# St1x.net
KiCad netlist of a schematic drawn in Altium Designer
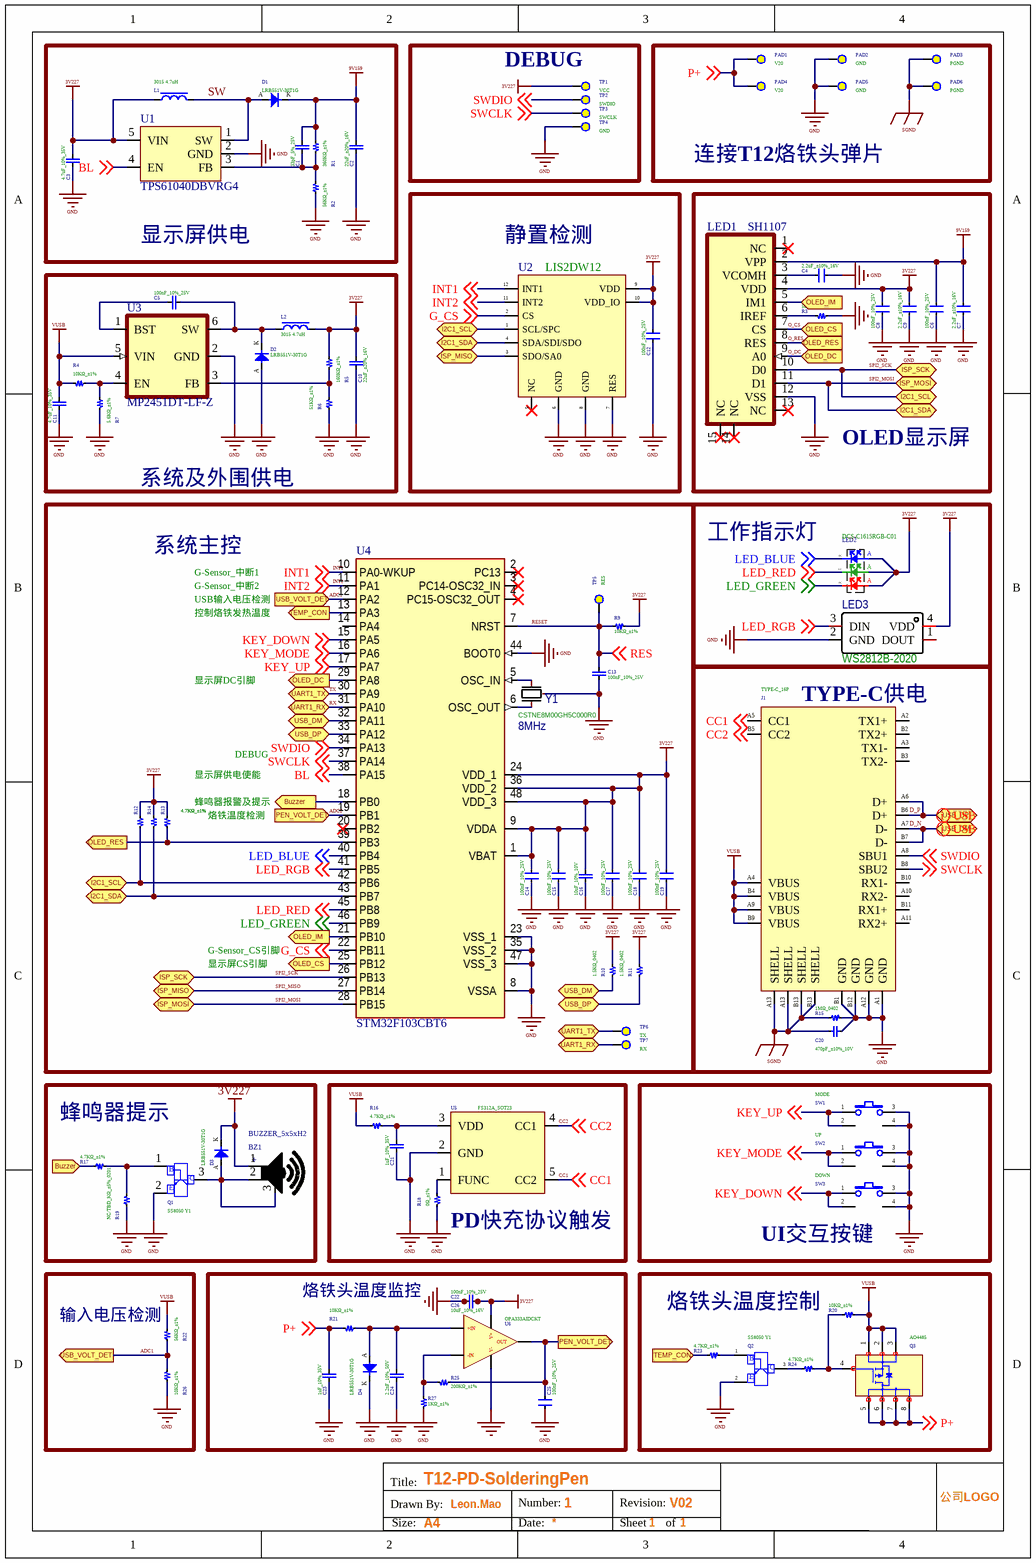
[diagram p0: St1x.SchDoc]

(export (version "E")
  (design (tool "Eeschema 10.0.6"))
  (components
    (comp (ref "BZ1")
      (value "BUZZER_5x5xH2")
      (footprint "BUZ-SMD_GSC5025YA")
      (description "电磁无源蜂鸣器(外部驱动)")
      (libsource (lib "SCHLIB_2022") (part "BZ"))
    )
    (comp (ref "C1")
      (value "33pF_5%_25V")
      (footprint "C1U0402")
      (description "贴片电容")
      (libsource (lib "SCHLIB_2022") (part "CAP_NP"))
    )
    (comp (ref "C2")
      (value "22uF_±20%_16V")
      (footprint "CL0603")
      (description "贴片电容")
      (libsource (lib "SCHLIB_2022") (part "CAP_NP"))
    )
    (comp (ref "C3")
      (value "4.7uF_10%_35V")
      (footprint "C4U0402")
      (description "贴片电容")
      (libsource (lib "SCHLIB_2022") (part "CAP_NP"))
    )
    (comp (ref "C4")
      (value "2.2uF_±10%_16V")
      (footprint "C4U0402")
      (description "贴片电容")
      (libsource (lib "") (part "CAP_NP_1"))
    )
    (comp (ref "C5")
      (value "100nF_10%_25V")
      (footprint "C1U0402")
      (description "贴片电容")
      (libsource (lib "SCHLIB_2022") (part "CAP_NP"))
    )
    (comp (ref "C6")
      (value "100nF_10%_25V")
      (footprint "C1U0402")
      (description "贴片电容")
      (libsource (lib "") (part "CAP_NP_1"))
    )
    (comp (ref "C7")
      (value "2.2uF_±10%_16V")
      (footprint "C4U0402")
      (description "贴片电容")
      (libsource (lib "") (part "CAP_NP_1"))
    )
    (comp (ref "C8")
      (value "100nF_10%_25V")
      (footprint "C1U0402")
      (description "贴片电容")
      (libsource (lib "") (part "CAP_NP_1"))
    )
    (comp (ref "C9")
      (value "2.2uF_±10%_16V")
      (footprint "C4U0402")
      (description "贴片电容")
      (libsource (lib "") (part "CAP_NP_1"))
    )
    (comp (ref "C10")
      (value "22uF_±20%_16V")
      (footprint "CL0603")
      (description "贴片电容")
      (libsource (lib "SCHLIB_2022") (part "CAP_NP"))
    )
    (comp (ref "C11")
      (value "4.7uF_10%_35V")
      (footprint "C4U0402")
      (description "贴片电容")
      (libsource (lib "SCHLIB_2022") (part "CAP_NP"))
    )
    (comp (ref "C12")
      (value "100nF_10%_25V")
      (footprint "C1U0402")
      (description "贴片电容")
      (libsource (lib "") (part "CAP_NP_1"))
    )
    (comp (ref "C13")
      (value "100nF_10%_25V")
      (footprint "C1U0402")
      (description "贴片电容")
      (libsource (lib "SCHLIB_2022") (part "CAP_NP"))
    )
    (comp (ref "C14")
      (value "100nF_10%_25V")
      (footprint "C1U0402")
      (description "贴片电容")
      (libsource (lib "") (part "CAP_NP_1"))
    )
    (comp (ref "C15")
      (value "100nF_10%_25V")
      (footprint "C1U0402")
      (description "贴片电容")
      (libsource (lib "") (part "CAP_NP_1"))
    )
    (comp (ref "C16")
      (value "10uF_10%_10V")
      (footprint "C4U0402")
      (description "贴片电容")
      (libsource (lib "SCHLIB_2022") (part "CAP_NP"))
    )
    (comp (ref "C17")
      (value "100nF_10%_25V")
      (footprint "C1U0402")
      (description "贴片电容")
      (libsource (lib "") (part "CAP_NP_1"))
    )
    (comp (ref "C18")
      (value "100nF_10%_25V")
      (footprint "C1U0402")
      (description "贴片电容")
      (libsource (lib "") (part "CAP_NP_1"))
    )
    (comp (ref "C19")
      (value "100nF_10%_25V")
      (footprint "C1U0402")
      (description "贴片电容")
      (libsource (lib "") (part "CAP_NP_1"))
    )
    (comp (ref "C20")
      (value "470pF_±10%_10V")
      (footprint "C0402")
      (description "贴片电容")
      (libsource (lib "Leon") (part "CAP NP_1"))
    )
    (comp (ref "C21")
      (value "1uF_10%_35V")
      (footprint "C1U0402")
      (description "贴片电容")
      (libsource (lib "SCHLIB_2022") (part "CAP_NP"))
    )
    (comp (ref "C22")
      (value "100nF_10%_25V")
      (footprint "C1U0402")
      (description "贴片电容")
      (libsource (lib "SCHLIB_2022") (part "CAP_NP"))
    )
    (comp (ref "C23")
      (value "1uF_10%_35V")
      (footprint "C1U0402")
      (description "贴片电容")
      (libsource (lib "SCHLIB_2022") (part "CAP_NP"))
    )
    (comp (ref "C24")
      (value "2.2nF_10%_50V")
      (footprint "C4U0402")
      (description "贴片电容")
      (libsource (lib "SCHLIB_2022") (part "CAP_NP"))
    )
    (comp (ref "C25")
      (value "100nF_10%_25V")
      (footprint "C1U0402")
      (description "贴片电容")
      (libsource (lib "") (part "CAP_NP_1"))
    )
    (comp (ref "C26")
      (value "10uF_10%_16V")
      (footprint "C4U0402")
      (description "贴片电容")
      (libsource (lib "SCHLIB_2022") (part "CAP_NP"))
    )
    (comp (ref "D1")
      (value "LRB551V-30T1G")
      (footprint "SOD-323_AK")
      (description "肖特基二极管")
      (libsource (lib "Leon") (part "DIODE"))
    )
    (comp (ref "D2")
      (value "LRB551V-30T1G")
      (footprint "SOD-323_AK")
      (description "肖特基二极管")
      (libsource (lib "Leon") (part "DIODE"))
    )
    (comp (ref "D3")
      (value "LRB551V-30T1G")
      (footprint "SOD-323_AK")
      (description "肖特基二极管")
      (libsource (lib "Leon") (part "DIODE"))
    )
    (comp (ref "D4")
      (value "LRB551V-30T1G")
      (footprint "SOD-323_AK")
      (description "肖特基二极管")
      (libsource (lib "Leon") (part "DIODE"))
    )
    (comp (ref "J1")
      (value "TYPE-C_16P")
      (footprint "TYPE-C_16P")
      (description "TYPE-C母座")
      (libsource (lib "Leon") (part "TYPE-C_RI"))
    )
    (comp (ref "L1")
      (value "3015 4.7uH")
      (footprint "INDC3015")
      (description "功率电感")
      (libsource (lib "SCHLIB_2022") (part "INDUCTOR_2"))
    )
    (comp (ref "L2")
      (value "3015 4.7uH")
      (footprint "INDC3015")
      (description "功率电感")
      (libsource (lib "") (part "INDUCTOR_2_1"))
    )
    (comp (ref "LED1")
      (value "SH1107")
      (footprint "CON_13P_0.7mm-FPC")
      (description "QG-2880TSWKG01")
      (fields
        (field (name "MF") "{'manufacturer': u'Texas Instruments'}")
        (field (name "MP") "LP2985AIM5-5.0")
      )
      (libsource (lib "SCHLIB_2022") (part "SH1107"))
    )
    (comp (ref "LED2")
      (value "DCS-C1615RGB-C01")
      (footprint "RGB_DCS-C1615RGB-C01")
      (description "红绿蓝三色发光二极管")
      (libsource (lib "Leon") (part "LED_RGBS"))
    )
    (comp (ref "LED3")
      (value "WS2812B-2020")
      (footprint "LED_2020")
      (fields (field (name "MANUFACTURER PART") "Yo-WS2812B-3528反贴雾状"))
      (libsource (lib "altium-import") (part "root_0_mirrored_YO-WS2812B-3528反贴_"))
    )
    (comp (ref "PAD1") (value "V20") (footprint "TP_A") (libsource (lib "SCHLIB_2022") (part "TEST")))
    (comp (ref "PAD2") (value "GND") (footprint "TP_A") (libsource (lib "SCHLIB_2022") (part "TEST")))
    (comp (ref "PAD3") (value "PGND") (footprint "TP_A") (libsource (lib "SCHLIB_2022") (part "TEST")))
    (comp (ref "PAD4") (value "V20") (footprint "TP_A") (libsource (lib "SCHLIB_2022") (part "TEST")))
    (comp (ref "PAD5") (value "GND") (footprint "TP_A") (libsource (lib "SCHLIB_2022") (part "TEST")))
    (comp (ref "PAD6") (value "PGND") (footprint "TP_A") (libsource (lib "SCHLIB_2022") (part "TEST")))
    (comp (ref "Q1")
      (value "SS8050 Y1")
      (footprint "SOT-23_123")
      (description "NPN三极管")
      (libsource (lib "PCBDEV_Library") (part "NPN"))
    )
    (comp (ref "Q2")
      (value "SS8050 Y1")
      (footprint "SOT-23_123")
      (description "NPN三极管")
      (libsource (lib "SCHLIB_2022") (part "NPN"))
    )
    (comp (ref "Q3")
      (value "AO4485")
      (footprint "SO-8M")
      (description "P沟道 40V 10A")
      (libsource (lib "SCHLIB_2022") (part "AO4485"))
    )
    (comp (ref "R1")
      (value "360KΩ_±1%")
      (footprint "RN0402")
      (description "贴片电阻")
      (libsource (lib "Leon") (part "ResSemi_3"))
    )
    (comp (ref "R2")
      (value "56KΩ_±1%")
      (footprint "RN0402")
      (description "贴片电阻")
      (libsource (lib "Leon") (part "ResSemi_3"))
    )
    (comp (ref "R3")
      (value "560kΩ_±1%")
      (footprint "RN0402")
      (description "贴片电阻")
      (libsource (lib "Leon") (part "ResSemi_3"))
    )
    (comp (ref "R4")
      (value "10KΩ_±1%")
      (footprint "RN0402")
      (description "贴片电阻")
      (libsource (lib "Leon") (part "ResSemi_3"))
    )
    (comp (ref "R5")
      (value "160KΩ_±1%")
      (footprint "RN0402")
      (description "贴片电阻")
      (libsource (lib "Leon") (part "ResSemi_3"))
    )
    (comp (ref "R6")
      (value "51KΩ_±1%")
      (footprint "RN0402")
      (description "贴片电阻")
      (libsource (lib "Leon") (part "ResSemi_3"))
    )
    (comp (ref "R7")
      (value "5.6KΩ_±1%")
      (footprint "RN0402")
      (description "贴片电阻")
      (libsource (lib "Leon") (part "ResSemi_3"))
    )
    (comp (ref "R9")
      (value "10KΩ_±1%")
      (footprint "RN0402")
      (description "贴片电阻")
      (libsource (lib "Leon") (part "ResSemi_3"))
    )
    (comp (ref "R10")
      (value "1.5KΩ_0402")
      (footprint "RN0402")
      (description "贴片电阻")
      (libsource (lib "Leon") (part "ResSemi_3"))
    )
    (comp (ref "R11")
      (value "1.5KΩ_0402")
      (footprint "RN0402")
      (description "贴片电阻")
      (libsource (lib "Leon") (part "ResSemi_3"))
    )
    (comp (ref "R12")
      (value "4.7KΩ_±1%")
      (footprint "RN0402")
      (description "贴片电阻")
      (libsource (lib "Leon") (part "ResSemi_3"))
    )
    (comp (ref "R13")
      (value "4.7KΩ_±1%")
      (footprint "RN0402")
      (description "贴片电阻")
      (libsource (lib "Leon") (part "ResSemi_3"))
    )
    (comp (ref "R14")
      (value "4.7KΩ_±1%")
      (footprint "RN0402")
      (description "贴片电阻")
      (libsource (lib "Leon") (part "ResSemi_3"))
    )
    (comp (ref "R15")
      (value "1MΩ_0402")
      (footprint "RN0402")
      (description "贴片电阻")
      (libsource (lib "Leon") (part "ResSemi_3"))
    )
    (comp (ref "R16")
      (value "4.7KΩ_±1%")
      (footprint "RN0402")
      (description "贴片电阻")
      (libsource (lib "Leon") (part "ResSemi_3"))
    )
    (comp (ref "R17")
      (value "4.7KΩ_±1%")
      (footprint "RN0402")
      (description "贴片电阻")
      (libsource (lib "Leon") (part "ResSemi_3"))
    )
    (comp (ref "R18")
      (value "0Ω_±1%")
      (footprint "RN0402")
      (description "贴片电阻")
      (libsource (lib "Leon") (part "ResSemi_3"))
    )
    (comp (ref "R19")
      (value "NC/TBD_KΩ_±5%_0201")
      (footprint "RN0402")
      (description "贴片电阻")
      (libsource (lib "Leon") (part "ResSemi_3"))
    )
    (comp (ref "R20")
      (value "10KΩ_±1%")
      (footprint "RN0402")
      (description "贴片电阻")
      (libsource (lib "Leon") (part "ResSemi_3"))
    )
    (comp (ref "R21")
      (value "10KΩ_±1%")
      (footprint "RN0603")
      (description "贴片电阻")
      (libsource (lib "Leon") (part "ResSemi_3"))
    )
    (comp (ref "R22")
      (value "56KΩ_±1%")
      (footprint "RN0402")
      (description "贴片电阻")
      (libsource (lib "Leon") (part "ResSemi_3"))
    )
    (comp (ref "R23")
      (value "4.7KΩ_±1%")
      (footprint "RN0402")
      (description "贴片电阻")
      (libsource (lib "Leon") (part "ResSemi_3"))
    )
    (comp (ref "R24")
      (value "4.7KΩ_±1%")
      (footprint "RN0402")
      (description "贴片电阻")
      (libsource (lib "Leon") (part "ResSemi_3"))
    )
    (comp (ref "R25")
      (value "200KΩ_±1%")
      (footprint "RN0402")
      (description "贴片电阻")
      (libsource (lib "Leon") (part "ResSemi_3"))
    )
    (comp (ref "R26")
      (value "10KΩ_±1%")
      (footprint "RN0402")
      (description "贴片电阻")
      (libsource (lib "Leon") (part "ResSemi_3"))
    )
    (comp (ref "R27")
      (value "1KΩ_±1%")
      (footprint "RN0402")
      (description "贴片电阻")
      (libsource (lib "Leon") (part "ResSemi_3"))
    )
    (comp (ref "SW1")
      (value "MODE")
      (footprint "KEY-SMD_4P-L4.2-W3.2-P2.20-LS5.1-TL")
      (description "轻触开关")
      (libsource (lib "SCHLIB_2022") (part "SW PUSHBUTTON"))
    )
    (comp (ref "SW2")
      (value "UP")
      (footprint "KEY-SMD_4P-L4.2-W3.2-P2.20-LS5.1-TL")
      (description "轻触开关")
      (libsource (lib "SCHLIB_2022") (part "SW PUSHBUTTON"))
    )
    (comp (ref "SW3")
      (value "DOWN")
      (footprint "KEY-SMD_4P-L4.2-W3.2-P2.20-LS5.1-TL")
      (description "轻触开关")
      (libsource (lib "SCHLIB_2022") (part "SW PUSHBUTTON"))
    )
    (comp (ref "TP1") (value "VCC") (footprint "SMD0808") (libsource (lib "SCHLIB_2022") (part "TEST")))
    (comp (ref "TP2") (value "SWDIO") (footprint "SMD0808") (libsource (lib "SCHLIB_2022") (part "TEST")))
    (comp (ref "TP3") (value "SWCLK") (footprint "SMD0808") (libsource (lib "SCHLIB_2022") (part "TEST")))
    (comp (ref "TP4") (value "GND") (footprint "SMD0808") (libsource (lib "SCHLIB_2022") (part "TEST")))
    (comp (ref "TP5") (value "RES") (footprint "SMD0808") (libsource (lib "SCHLIB_2022") (part "TEST")))
    (comp (ref "TP6") (value "TX") (footprint "SMD0808") (libsource (lib "SCHLIB_2022") (part "TEST")))
    (comp (ref "TP7") (value "RX") (footprint "SMD0808") (libsource (lib "SCHLIB_2022") (part "TEST")))
    (comp (ref "U1")
      (value "TPS61040DBVRG4")
      (footprint "SOT23-5")
      (description "DC-DC芯片")
      (libsource (lib "SCHLIB_2022") (part "TPS61040DBVRG4_[C7722]"))
    )
    (comp (ref "U2")
      (value "LIS2DW12")
      (footprint "LGA12_20x20x07")
      (libsource (lib "SCHLIB_2022") (part "LIS2DW12"))
    )
    (comp (ref "U3")
      (value "MP2451DT-LF-Z")
      (footprint "SOT23-6")
      (fields
        (field (name "MF") "{'manufacturer': u'Texas Instruments'}")
        (field (name "MP") "LP2985AIM5-5.0")
      )
      (libsource (lib "SCHLIB_2022") (part "MP2451DT-LF-Z"))
    )
    (comp (ref "U4")
      (value "STM32F103CBT6")
      (footprint "LQFP48-7x7mm")
      (description "No Description Available")
      (fields (field (name "COPYRIGHT") "Copyright (C) 2023 Ultra Librarian. All rights reserved."))
      (libsource (lib "SCHLIB_2022") (part "STM32F103CBT6"))
    )
    (comp (ref "U5")
      (value "FS312A_SOT23")
      (footprint "SOT23-5")
      (description "USB Type-C PD快充协议智能触发芯片")
      (libsource (lib "SCHLIB_2022") (part "FS312A"))
    )
    (comp (ref "U6")
      (value "OPA333AIDCKT")
      (footprint "SOT23-5")
      (libsource (lib "SCHLIB_2022") (part "OPA333_SOT23"))
    )
    (comp (ref "Y1")
      (value "CSTNE8M00GH5C000R0")
      (footprint "OSC-SMD_3P-L3.2-W1.3-P1.20-L")
      (description "频率:8MHz;频率容差:±0.07%;内藏负载电容:33pF;谐振阻抗:40Ω;")
      (fields (field (name "MANUFACTURER") "muRata(村田)") (field (name "ALTIUM_VALUE") "8MHz"))
      (libsource (lib "SCHLIB_2022") (part "CSTNE8M00GH5C000R0"))
    )
  )
  (nets
    (net (code "1") (name "/ADC1") (class "Default")
      (node (ref "R22") (pin "1") (pinfunction "1_1") (pintype "passive"))
      (node (ref "R26") (pin "2") (pinfunction "2_2") (pintype "passive"))
      (node (ref "U4") (pin "12") (pinfunction "PA2_12") (pintype "bidirectional"))
    )
    (net (code "2") (name "/ADC2") (class "Default")
      (node (ref "C25") (pin "1") (pinfunction "1_1") (pintype "passive"))
      (node (ref "R25") (pin "1") (pinfunction "1_1") (pintype "passive"))
      (node (ref "U4") (pin "19") (pinfunction "PB1_19") (pintype "bidirectional"))
      (node (ref "U6") (pin "1") (pinfunction "OUT_1") (pintype "passive"))
    )
    (net (code "3") (name "/Buzzer") (class "Default")
      (node (ref "R17") (pin "1") (pinfunction "1_1") (pintype "passive"))
      (node (ref "U4") (pin "18") (pinfunction "PB0_18") (pintype "bidirectional"))
    )
    (net (code "4") (name "/D_N") (class "Default")
      (node (ref "J1") (pin "A7") (pinfunction "D-_A7") (pintype "passive"))
      (node (ref "J1") (pin "B7") (pinfunction "D-_B7") (pintype "passive"))
      (node (ref "R10") (pin "2") (pinfunction "2_2") (pintype "passive"))
      (node (ref "U4") (pin "32") (pinfunction "PA11_32") (pintype "bidirectional"))
    )
    (net (code "5") (name "/D_P") (class "Default")
      (node (ref "J1") (pin "A6") (pinfunction "D+_A6") (pintype "passive"))
      (node (ref "J1") (pin "B6") (pinfunction "D+_B6") (pintype "passive"))
      (node (ref "R11") (pin "2") (pinfunction "2_2") (pintype "passive"))
      (node (ref "U4") (pin "33") (pinfunction "PA12_33") (pintype "bidirectional"))
    )
    (net (code "6") (name "/OLED_IM") (class "Default")
      (node (ref "LED1") (pin "5") (pinfunction "IM1_5") (pintype "passive"))
      (node (ref "U4") (pin "21") (pinfunction "PB10_21") (pintype "bidirectional"))
    )
    (net (code "7") (name "/O_CS") (class "Default")
      (node (ref "LED1") (pin "7") (pinfunction "CS_7") (pintype "passive"))
      (node (ref "U4") (pin "25") (pinfunction "PB12_25") (pintype "bidirectional"))
    )
    (net (code "8") (name "/O_DC") (class "Default")
      (node (ref "LED1") (pin "9") (pinfunction "A0_9") (pintype "input"))
      (node (ref "U4") (pin "29") (pinfunction "PA8_29") (pintype "bidirectional"))
    )
    (net (code "9") (name "/O_RES") (class "Default")
      (node (ref "LED1") (pin "8") (pinfunction "RES_8") (pintype "passive"))
      (node (ref "R13") (pin "2") (pinfunction "2_2") (pintype "passive"))
      (node (ref "U4") (pin "39") (pinfunction "PB3_39") (pintype "bidirectional"))
    )
    (net (code "10") (name "/RX") (class "Default")
      (node (ref "TP7") (pin "1") (pinfunction "1_1") (pintype "passive"))
      (node (ref "U4") (pin "31") (pinfunction "PA10_31") (pintype "bidirectional"))
    )
    (net (code "11") (name "/SPI2_MISO") (class "Default")
      (node (ref "U2") (pin "3") (pinfunction "SDO/SA0_3") (pintype "passive"))
      (node (ref "U4") (pin "27") (pinfunction "PB14_27") (pintype "bidirectional"))
    )
    (net (code "12") (name "/SPI2_MOSI") (class "Default")
      (node (ref "LED1") (pin "11") (pinfunction "D1_11") (pintype "passive"))
      (node (ref "R14") (pin "1") (pinfunction "1_1") (pintype "passive"))
      (node (ref "U2") (pin "4") (pinfunction "SDA/SDI/SDO_4") (pintype "passive"))
      (node (ref "U4") (pin "28") (pinfunction "PB15_28") (pintype "bidirectional"))
      (node (ref "U4") (pin "43") (pinfunction "PB7_43") (pintype "bidirectional"))
    )
    (net (code "13") (name "/SPI2_SCK") (class "Default")
      (node (ref "LED1") (pin "10") (pinfunction "D0_10") (pintype "passive"))
      (node (ref "R12") (pin "1") (pinfunction "1_1") (pintype "passive"))
      (node (ref "U2") (pin "1") (pinfunction "SCL/SPC_1") (pintype "passive"))
      (node (ref "U4") (pin "26") (pinfunction "PB13_26") (pintype "bidirectional"))
      (node (ref "U4") (pin "42") (pinfunction "PB6_42") (pintype "bidirectional"))
    )
    (net (code "14") (name "/SW") (class "Default")
      (node (ref "D1") (pin "A") (pinfunction "ANODE_A") (pintype "passive"))
      (node (ref "L1") (pin "2") (pinfunction "2_2") (pintype "passive"))
      (node (ref "U1") (pin "1") (pinfunction "SW_1") (pintype "passive"))
    )
    (net (code "15") (name "/TEMP_CON") (class "Default")
      (node (ref "R23") (pin "1") (pinfunction "1_1") (pintype "passive"))
      (node (ref "U4") (pin "13") (pinfunction "PA3_13") (pintype "bidirectional"))
    )
    (net (code "16") (name "/TX") (class "Default")
      (node (ref "TP6") (pin "1") (pinfunction "1_1") (pintype "passive"))
      (node (ref "U4") (pin "30") (pinfunction "PA9_30") (pintype "bidirectional"))
    )
    (net (code "17") (name "3V227") (class "Default")
      (node (ref "BZ1") (pin "1") (pinfunction "+_1") (pintype "passive"))
      (node (ref "C10") (pin "2") (pinfunction "2_2") (pintype "passive"))
      (node (ref "C12") (pin "1") (pinfunction "1_1") (pintype "passive"))
      (node (ref "C14") (pin "1") (pinfunction "1_1") (pintype "passive"))
      (node (ref "C15") (pin "1") (pinfunction "1_1") (pintype "passive"))
      (node (ref "C16") (pin "2") (pinfunction "2_2") (pintype "passive"))
      (node (ref "C17") (pin "1") (pinfunction "1_1") (pintype "passive"))
      (node (ref "C18") (pin "1") (pinfunction "1_1") (pintype "passive"))
      (node (ref "C19") (pin "1") (pinfunction "1_1") (pintype "passive"))
      (node (ref "C22") (pin "2") (pinfunction "2_2") (pintype "passive"))
      (node (ref "C26") (pin "1") (pinfunction "1_1") (pintype "passive"))
      (node (ref "C3") (pin "2") (pinfunction "2_2") (pintype "passive"))
      (node (ref "C8") (pin "1") (pinfunction "1_1") (pintype "passive"))
      (node (ref "C9") (pin "1") (pinfunction "1_1") (pintype "passive"))
      (node (ref "D3") (pin "K") (pinfunction "CATHODE_K") (pintype "passive"))
      (node (ref "L1") (pin "1") (pinfunction "1_1") (pintype "passive"))
      (node (ref "L2") (pin "1") (pinfunction "1_1") (pintype "passive"))
      (node (ref "LED1") (pin "4") (pinfunction "VDD_4") (pintype "power_in"))
      (node (ref "LED2") (pin "A") (pinfunction "A_A") (pintype "passive"))
      (node (ref "LED3") (pin "4") (pinfunction "VDD_4") (pintype "passive"))
      (node (ref "R10") (pin "1") (pinfunction "1_1") (pintype "passive"))
      (node (ref "R11") (pin "1") (pinfunction "1_1") (pintype "passive"))
      (node (ref "R12") (pin "2") (pinfunction "2_2") (pintype "passive"))
      (node (ref "R13") (pin "1") (pinfunction "1_1") (pintype "passive"))
      (node (ref "R14") (pin "2") (pinfunction "2_2") (pintype "passive"))
      (node (ref "R5") (pin "1") (pinfunction "1_1") (pintype "passive"))
      (node (ref "R9") (pin "1") (pinfunction "1_1") (pintype "passive"))
      (node (ref "TP1") (pin "1") (pinfunction "1_1") (pintype "passive"))
      (node (ref "U1") (pin "5") (pinfunction "VIN_5") (pintype "passive"))
      (node (ref "U2") (pin "10") (pinfunction "VDD_IO_10") (pintype "passive"))
      (node (ref "U2") (pin "9") (pinfunction "VDD_9") (pintype "passive"))
      (node (ref "U4") (pin "1") (pinfunction "VBAT_1") (pintype "power_in"))
      (node (ref "U4") (pin "24") (pinfunction "VDD_1_24") (pintype "power_in"))
      (node (ref "U4") (pin "36") (pinfunction "VDD_2_36") (pintype "power_in"))
      (node (ref "U4") (pin "48") (pinfunction "VDD_3_48") (pintype "power_in"))
      (node (ref "U4") (pin "9") (pinfunction "VDDA_9") (pintype "power_in"))
      (node (ref "U6") (pin "5") (pinfunction "V+_5") (pintype "passive"))
    )
    (net (code "18") (name "9V159") (class "Default")
      (node (ref "C1") (pin "2") (pinfunction "2_2") (pintype "passive"))
      (node (ref "C2") (pin "2") (pinfunction "2_2") (pintype "passive"))
      (node (ref "C6") (pin "1") (pinfunction "1_1") (pintype "passive"))
      (node (ref "C7") (pin "1") (pinfunction "1_1") (pintype "passive"))
      (node (ref "D1") (pin "K") (pinfunction "CATHODE_K") (pintype "passive"))
      (node (ref "LED1") (pin "2") (pinfunction "VPP_2") (pintype "power_in"))
      (node (ref "R1") (pin "1") (pinfunction "1_1") (pintype "passive"))
    )
    (net (code "19") (name "BL") (class "Default")
      (node (ref "U1") (pin "4") (pinfunction "EN_4") (pintype "passive"))
      (node (ref "U4") (pin "38") (pinfunction "PA15_38") (pintype "bidirectional"))
    )
    (net (code "20") (name "CC1") (class "Default")
      (node (ref "J1") (pin "A5") (pinfunction "CC1_A5") (pintype "passive"))
      (node (ref "U5") (pin "5") (pinfunction "CC2_5") (pintype "passive"))
    )
    (net (code "21") (name "CC2") (class "Default")
      (node (ref "J1") (pin "B5") (pinfunction "CC2_B5") (pintype "passive"))
      (node (ref "U5") (pin "4") (pinfunction "CC1_4") (pintype "passive"))
    )
    (net (code "22") (name "GND") (class "Default")
      (node (ref "C10") (pin "1") (pinfunction "1_1") (pintype "passive"))
      (node (ref "C11") (pin "1") (pinfunction "1_1") (pintype "passive"))
      (node (ref "C12") (pin "2") (pinfunction "2_2") (pintype "passive"))
      (node (ref "C13") (pin "2") (pinfunction "2_2") (pintype "passive"))
      (node (ref "C14") (pin "2") (pinfunction "2_2") (pintype "passive"))
      (node (ref "C15") (pin "2") (pinfunction "2_2") (pintype "passive"))
      (node (ref "C16") (pin "1") (pinfunction "1_1") (pintype "passive"))
      (node (ref "C17") (pin "2") (pinfunction "2_2") (pintype "passive"))
      (node (ref "C18") (pin "2") (pinfunction "2_2") (pintype "passive"))
      (node (ref "C19") (pin "2") (pinfunction "2_2") (pintype "passive"))
      (node (ref "C2") (pin "1") (pinfunction "1_1") (pintype "passive"))
      (node (ref "C20") (pin "1") (pinfunction "1_1") (pintype "passive"))
      (node (ref "C21") (pin "1") (pinfunction "1_1") (pintype "passive"))
      (node (ref "C22") (pin "1") (pinfunction "1_1") (pintype "passive"))
      (node (ref "C23") (pin "2") (pinfunction "2_2") (pintype "passive"))
      (node (ref "C24") (pin "2") (pinfunction "2_2") (pintype "passive"))
      (node (ref "C25") (pin "2") (pinfunction "2_2") (pintype "passive"))
      (node (ref "C26") (pin "2") (pinfunction "2_2") (pintype "passive"))
      (node (ref "C3") (pin "1") (pinfunction "1_1") (pintype "passive"))
      (node (ref "C4") (pin "2") (pinfunction "2_2") (pintype "passive"))
      (node (ref "C6") (pin "2") (pinfunction "2_2") (pintype "passive"))
      (node (ref "C7") (pin "2") (pinfunction "2_2") (pintype "passive"))
      (node (ref "C8") (pin "2") (pinfunction "2_2") (pintype "passive"))
      (node (ref "C9") (pin "2") (pinfunction "2_2") (pintype "passive"))
      (node (ref "D2") (pin "A") (pinfunction "ANODE_A") (pintype "passive"))
      (node (ref "D4") (pin "K") (pinfunction "CATHODE_K") (pintype "passive"))
      (node (ref "J1") (pin "A1") (pinfunction "GND_A1") (pintype "passive"))
      (node (ref "J1") (pin "A12") (pinfunction "GND_A12") (pintype "passive"))
      (node (ref "J1") (pin "B1") (pinfunction "GND_B1") (pintype "passive"))
      (node (ref "J1") (pin "B12") (pinfunction "GND_B12") (pintype "passive"))
      (node (ref "LED1") (pin "12") (pinfunction "VSS_12") (pintype "passive"))
      (node (ref "LED3") (pin "2") (pinfunction "GND_2") (pintype "passive"))
      (node (ref "PAD2") (pin "1") (pinfunction "1_1") (pintype "passive"))
      (node (ref "PAD5") (pin "1") (pinfunction "1_1") (pintype "passive"))
      (node (ref "Q1") (pin "2") (pinfunction "EMITTER_2") (pintype "passive"))
      (node (ref "Q2") (pin "2") (pinfunction "EMITTER_2") (pintype "passive"))
      (node (ref "R15") (pin "2") (pinfunction "2_2") (pintype "passive"))
      (node (ref "R18") (pin "2") (pinfunction "2_2") (pintype "passive"))
      (node (ref "R19") (pin "1") (pinfunction "1_1") (pintype "passive"))
      (node (ref "R2") (pin "1") (pinfunction "1_1") (pintype "passive"))
      (node (ref "R26") (pin "1") (pinfunction "1_1") (pintype "passive"))
      (node (ref "R27") (pin "2") (pinfunction "2_2") (pintype "passive"))
      (node (ref "R3") (pin "1") (pinfunction "1_1") (pintype "passive"))
      (node (ref "R6") (pin "1") (pinfunction "1_1") (pintype "passive"))
      (node (ref "R7") (pin "2") (pinfunction "2_2") (pintype "passive"))
      (node (ref "SW1") (pin "3") (pinfunction "3_3") (pintype "passive"))
      (node (ref "SW1") (pin "4") (pinfunction "4_4") (pintype "passive"))
      (node (ref "SW2") (pin "3") (pinfunction "3_3") (pintype "passive"))
      (node (ref "SW2") (pin "4") (pinfunction "4_4") (pintype "passive"))
      (node (ref "SW3") (pin "3") (pinfunction "3_3") (pintype "passive"))
      (node (ref "SW3") (pin "4") (pinfunction "4_4") (pintype "passive"))
      (node (ref "TP4") (pin "1") (pinfunction "1_1") (pintype "passive"))
      (node (ref "U1") (pin "2") (pinfunction "GND_2") (pintype "passive"))
      (node (ref "U2") (pin "6") (pinfunction "GND_6") (pintype "passive"))
      (node (ref "U2") (pin "7") (pinfunction "RES_7") (pintype "passive"))
      (node (ref "U2") (pin "8") (pinfunction "GND_8") (pintype "passive"))
      (node (ref "U3") (pin "2") (pinfunction "GND_2") (pintype "power_in"))
      (node (ref "U4") (pin "23") (pinfunction "VSS_1_23") (pintype "power_in"))
      (node (ref "U4") (pin "35") (pinfunction "VSS_2_35") (pintype "power_in"))
      (node (ref "U4") (pin "44") (pinfunction "BOOT0_44") (pintype "input"))
      (node (ref "U4") (pin "47") (pinfunction "VSS_3_47") (pintype "power_in"))
      (node (ref "U4") (pin "8") (pinfunction "VSSA_8") (pintype "power_in"))
      (node (ref "U5") (pin "2") (pinfunction "GND_2") (pintype "passive"))
      (node (ref "U6") (pin "2") (pinfunction "V-_2") (pintype "passive"))
      (node (ref "Y1") (pin "2") (pinfunction "GND_2") (pintype "passive"))
    )
    (net (code "23") (name "G_CS") (class "Default")
      (node (ref "U2") (pin "2") (pinfunction "CS_2") (pintype "passive"))
      (node (ref "U4") (pin "22") (pinfunction "PB11_22") (pintype "bidirectional"))
    )
    (net (code "24") (name "INT1") (class "Default")
      (node (ref "U2") (pin "12") (pinfunction "INT1_12") (pintype "passive"))
      (node (ref "U4") (pin "10") (pinfunction "PA0-WKUP_10") (pintype "bidirectional"))
    )
    (net (code "25") (name "INT2") (class "Default")
      (node (ref "U2") (pin "11") (pinfunction "INT2_11") (pintype "passive"))
      (node (ref "U4") (pin "11") (pinfunction "PA1_11") (pintype "bidirectional"))
    )
    (net (code "26") (name "KEY_DOWN") (class "Default")
      (node (ref "SW3") (pin "1") (pinfunction "1_1") (pintype "passive"))
      (node (ref "SW3") (pin "2") (pinfunction "2_2") (pintype "passive"))
      (node (ref "U4") (pin "15") (pinfunction "PA5_15") (pintype "bidirectional"))
    )
    (net (code "27") (name "KEY_MODE") (class "Default")
      (node (ref "SW2") (pin "1") (pinfunction "1_1") (pintype "passive"))
      (node (ref "SW2") (pin "2") (pinfunction "2_2") (pintype "passive"))
      (node (ref "U4") (pin "16") (pinfunction "PA6_16") (pintype "bidirectional"))
    )
    (net (code "28") (name "KEY_UP") (class "Default")
      (node (ref "SW1") (pin "1") (pinfunction "1_1") (pintype "passive"))
      (node (ref "SW1") (pin "2") (pinfunction "2_2") (pintype "passive"))
      (node (ref "U4") (pin "17") (pinfunction "PA7_17") (pintype "bidirectional"))
    )
    (net (code "29") (name "LED_BLUE") (class "Default")
      (node (ref "LED2") (pin "BC") (pinfunction "BC_BC") (pintype "passive"))
      (node (ref "U4") (pin "40") (pinfunction "PB4_40") (pintype "bidirectional"))
    )
    (net (code "30") (name "LED_GREEN") (class "Default")
      (node (ref "LED2") (pin "RC") (pinfunction "RC_RC") (pintype "passive"))
      (node (ref "U4") (pin "46") (pinfunction "PB9_46") (pintype "bidirectional"))
    )
    (net (code "31") (name "LED_RED") (class "Default")
      (node (ref "LED2") (pin "GC") (pinfunction "GC_GC") (pintype "passive"))
      (node (ref "U4") (pin "45") (pinfunction "PB8_45") (pintype "bidirectional"))
    )
    (net (code "32") (name "LED_RGB") (class "Default")
      (node (ref "LED3") (pin "3") (pinfunction "DIN_3") (pintype "passive"))
      (node (ref "U4") (pin "41") (pinfunction "PB5_41") (pintype "bidirectional"))
    )
    (net (code "33") (name "Net-(D2-CATHODE)") (class "Default")
      (node (ref "C5") (pin "1") (pinfunction "1_1") (pintype "passive"))
      (node (ref "D2") (pin "K") (pinfunction "CATHODE_K") (pintype "passive"))
      (node (ref "L2") (pin "2") (pinfunction "2_2") (pintype "passive"))
      (node (ref "U3") (pin "6") (pinfunction "SW_6") (pintype "passive"))
    )
    (net (code "34") (name "Net-(D3-ANODE)") (class "Default")
      (node (ref "BZ1") (pin "2") (pinfunction "-_2") (pintype "passive"))
      (node (ref "BZ1") (pin "3") (pinfunction "-_3") (pintype "passive"))
      (node (ref "D3") (pin "A") (pinfunction "ANODE_A") (pintype "passive"))
      (node (ref "Q1") (pin "3") (pinfunction "COLLECTOR_3") (pintype "passive"))
    )
    (net (code "35") (name "Net-(D4-ANODE)") (class "Default")
      (node (ref "C24") (pin "1") (pinfunction "1_1") (pintype "passive"))
      (node (ref "D4") (pin "A") (pinfunction "ANODE_A") (pintype "passive"))
      (node (ref "R21") (pin "1") (pinfunction "1_1") (pintype "passive"))
      (node (ref "U6") (pin "3") (pinfunction "+IN_3") (pintype "passive"))
    )
    (net (code "36") (name "Net-(LED1-IREF)") (class "Default")
      (node (ref "LED1") (pin "6") (pinfunction "IREF_6") (pintype "passive"))
      (node (ref "R3") (pin "2") (pinfunction "2_2") (pintype "passive"))
    )
    (net (code "37") (name "Net-(LED1-VCOMH)") (class "Default")
      (node (ref "C4") (pin "1") (pinfunction "1_1") (pintype "passive"))
      (node (ref "LED1") (pin "3") (pinfunction "VCOMH_3") (pintype "passive"))
    )
    (net (code "38") (name "Net-(Q1-BASE)") (class "Default")
      (node (ref "Q1") (pin "1") (pinfunction "BASE_1") (pintype "passive"))
      (node (ref "R17") (pin "2") (pinfunction "2_2") (pintype "passive"))
      (node (ref "R19") (pin "2") (pinfunction "2_2") (pintype "passive"))
    )
    (net (code "39") (name "Net-(Q2-BASE)") (class "Default")
      (node (ref "Q2") (pin "1") (pinfunction "BASE_1") (pintype "passive"))
      (node (ref "R23") (pin "2") (pinfunction "2_2") (pintype "passive"))
    )
    (net (code "40") (name "Net-(Q2-COLLECTOR)") (class "Default")
      (node (ref "Q2") (pin "3") (pinfunction "COLLECTOR_3") (pintype "passive"))
      (node (ref "R24") (pin "1") (pinfunction "1_1") (pintype "passive"))
    )
    (net (code "41") (name "Net-(Q3-G)") (class "Default")
      (node (ref "Q3") (pin "4") (pinfunction "G_4") (pintype "passive"))
      (node (ref "R20") (pin "1") (pinfunction "1_1") (pintype "passive"))
      (node (ref "R24") (pin "2") (pinfunction "2_2") (pintype "passive"))
    )
    (net (code "42") (name "Net-(U1-FB)") (class "Default")
      (node (ref "C1") (pin "1") (pinfunction "1_1") (pintype "passive"))
      (node (ref "R1") (pin "2") (pinfunction "2_2") (pintype "passive"))
      (node (ref "R2") (pin "2") (pinfunction "2_2") (pintype "passive"))
      (node (ref "U1") (pin "3") (pinfunction "FB_3") (pintype "passive"))
    )
    (net (code "43") (name "Net-(U3-BST)") (class "Default")
      (node (ref "C5") (pin "2") (pinfunction "2_2") (pintype "passive"))
      (node (ref "U3") (pin "1") (pinfunction "BST_1") (pintype "passive"))
    )
    (net (code "44") (name "Net-(U3-EN)") (class "Default")
      (node (ref "R4") (pin "1") (pinfunction "1_1") (pintype "passive"))
      (node (ref "R7") (pin "1") (pinfunction "1_1") (pintype "passive"))
      (node (ref "U3") (pin "4") (pinfunction "EN_4") (pintype "passive"))
    )
    (net (code "45") (name "Net-(U3-FB)") (class "Default")
      (node (ref "R5") (pin "2") (pinfunction "2_2") (pintype "passive"))
      (node (ref "R6") (pin "2") (pinfunction "2_2") (pintype "passive"))
      (node (ref "U3") (pin "3") (pinfunction "FB_3") (pintype "passive"))
    )
    (net (code "46") (name "Net-(U4-OSC_IN)") (class "Default")
      (node (ref "U4") (pin "5") (pinfunction "OSC_IN_5") (pintype "input"))
      (node (ref "Y1") (pin "1") (pinfunction "OSC1_1") (pintype "passive"))
    )
    (net (code "47") (name "Net-(U4-OSC_OUT)") (class "Default")
      (node (ref "U4") (pin "6") (pinfunction "OSC_OUT_6") (pintype "output"))
      (node (ref "Y1") (pin "3") (pinfunction "OSC2_3") (pintype "passive"))
    )
    (net (code "48") (name "Net-(U5-FUNC)") (class "Default")
      (node (ref "R18") (pin "1") (pinfunction "1_1") (pintype "passive"))
      (node (ref "U5") (pin "1") (pinfunction "FUNC_1") (pintype "passive"))
    )
    (net (code "49") (name "Net-(U5-VDD)") (class "Default")
      (node (ref "C21") (pin "2") (pinfunction "2_2") (pintype "passive"))
      (node (ref "R16") (pin "2") (pinfunction "2_2") (pintype "passive"))
      (node (ref "U5") (pin "3") (pinfunction "VDD_3") (pintype "passive"))
    )
    (net (code "50") (name "Net-(U6--IN)") (class "Default")
      (node (ref "R25") (pin "2") (pinfunction "2_2") (pintype "passive"))
      (node (ref "R27") (pin "1") (pinfunction "1_1") (pintype "passive"))
      (node (ref "U6") (pin "4") (pinfunction "-IN_4") (pintype "passive"))
    )
    (net (code "51") (name "P+") (class "Default")
      (node (ref "C23") (pin "1") (pinfunction "1_1") (pintype "passive"))
      (node (ref "PAD1") (pin "1") (pinfunction "1_1") (pintype "passive"))
      (node (ref "PAD4") (pin "1") (pinfunction "1_1") (pintype "passive"))
      (node (ref "Q3") (pin "5") (pinfunction "D_5") (pintype "passive"))
      (node (ref "Q3") (pin "6") (pinfunction "D_6") (pintype "passive"))
      (node (ref "Q3") (pin "7") (pinfunction "D_7") (pintype "passive"))
      (node (ref "Q3") (pin "8") (pinfunction "D_8") (pintype "passive"))
      (node (ref "R21") (pin "2") (pinfunction "2_2") (pintype "passive"))
    )
    (net (code "52") (name "RES") (class "Default")
      (node (ref "C13") (pin "1") (pinfunction "1_1") (pintype "passive"))
      (node (ref "R9") (pin "2") (pinfunction "2_2") (pintype "passive"))
      (node (ref "TP5") (pin "1") (pinfunction "1_1") (pintype "passive"))
      (node (ref "U4") (pin "7") (pinfunction "NRST_7") (pintype "bidirectional"))
    )
    (net (code "53") (name "SGND") (class "Default")
      (node (ref "C20") (pin "2") (pinfunction "2_2") (pintype "passive"))
      (node (ref "J1") (pin "A13") (pinfunction "SHELL_A13") (pintype "passive"))
      (node (ref "J1") (pin "B13") (pinfunction "SHELL_B13") (pintype "passive"))
      (node (ref "PAD3") (pin "1") (pinfunction "1_1") (pintype "passive"))
      (node (ref "PAD6") (pin "1") (pinfunction "1_1") (pintype "passive"))
      (node (ref "R15") (pin "1") (pinfunction "1_1") (pintype "passive"))
    )
    (net (code "54") (name "SWCLK") (class "Default")
      (node (ref "J1") (pin "B8") (pinfunction "SBU2_B8") (pintype "passive"))
      (node (ref "TP3") (pin "1") (pinfunction "1_1") (pintype "passive"))
      (node (ref "U4") (pin "37") (pinfunction "PA14_37") (pintype "bidirectional"))
    )
    (net (code "55") (name "SWDIO") (class "Default")
      (node (ref "J1") (pin "A8") (pinfunction "SBU1_A8") (pintype "passive"))
      (node (ref "TP2") (pin "1") (pinfunction "1_1") (pintype "passive"))
      (node (ref "U4") (pin "34") (pinfunction "PA13_34") (pintype "bidirectional"))
    )
    (net (code "56") (name "VUSB") (class "Default")
      (node (ref "C11") (pin "2") (pinfunction "2_2") (pintype "passive"))
      (node (ref "J1") (pin "A4") (pinfunction "VBUS_A4") (pintype "passive"))
      (node (ref "J1") (pin "A9") (pinfunction "VBUS_A9") (pintype "passive"))
      (node (ref "J1") (pin "B4") (pinfunction "VBUS_B4") (pintype "passive"))
      (node (ref "J1") (pin "B9") (pinfunction "VBUS_B9") (pintype "passive"))
      (node (ref "Q3") (pin "1") (pinfunction "S_1") (pintype "passive"))
      (node (ref "Q3") (pin "2") (pinfunction "S_2") (pintype "passive"))
      (node (ref "Q3") (pin "3") (pinfunction "S_3") (pintype "passive"))
      (node (ref "R16") (pin "1") (pinfunction "1_1") (pintype "passive"))
      (node (ref "R20") (pin "2") (pinfunction "2_2") (pintype "passive"))
      (node (ref "R22") (pin "2") (pinfunction "2_2") (pintype "passive"))
      (node (ref "R4") (pin "2") (pinfunction "2_2") (pintype "passive"))
      (node (ref "U3") (pin "5") (pinfunction "VIN_5") (pintype "input"))
    )
    (net (code "57") (name "unconnected-(J1-RX1+-PadB11)") (class "Default")
      (node (ref "J1") (pin "B11") (pinfunction "RX1+_B11") (pintype "passive"))
    )
    (net (code "58") (name "unconnected-(J1-RX1--PadB10)") (class "Default")
      (node (ref "J1") (pin "B10") (pinfunction "RX1-_B10") (pintype "passive"))
    )
    (net (code "59") (name "unconnected-(J1-RX2+-PadA11)") (class "Default")
      (node (ref "J1") (pin "A11") (pinfunction "RX2+_A11") (pintype "passive"))
    )
    (net (code "60") (name "unconnected-(J1-RX2--PadA10)") (class "Default")
      (node (ref "J1") (pin "A10") (pinfunction "RX2-_A10") (pintype "passive"))
    )
    (net (code "61") (name "unconnected-(J1-TX1+-PadA2)") (class "Default")
      (node (ref "J1") (pin "A2") (pinfunction "TX1+_A2") (pintype "passive"))
    )
    (net (code "62") (name "unconnected-(J1-TX1--PadA3)") (class "Default")
      (node (ref "J1") (pin "A3") (pinfunction "TX1-_A3") (pintype "passive"))
    )
    (net (code "63") (name "unconnected-(J1-TX2+-PadB2)") (class "Default")
      (node (ref "J1") (pin "B2") (pinfunction "TX2+_B2") (pintype "passive"))
    )
    (net (code "64") (name "unconnected-(J1-TX2--PadB3)") (class "Default")
      (node (ref "J1") (pin "B3") (pinfunction "TX2-_B3") (pintype "passive"))
    )
    (net (code "65") (name "unconnected-(LED1-NC-Pad1)") (class "Default")
      (node (ref "LED1") (pin "1") (pinfunction "NC_1") (pintype "passive+no_connect"))
    )
    (net (code "66") (name "unconnected-(LED1-NC-Pad13)") (class "Default")
      (node (ref "LED1") (pin "13") (pinfunction "NC_13") (pintype "passive+no_connect"))
    )
    (net (code "67") (name "unconnected-(LED1-NC-Pad14)") (class "Default")
      (node (ref "LED1") (pin "14") (pinfunction "NC_14") (pintype "passive+no_connect"))
    )
    (net (code "68") (name "unconnected-(LED1-NC-Pad15)") (class "Default")
      (node (ref "LED1") (pin "15") (pinfunction "NC_15") (pintype "passive+no_connect"))
    )
    (net (code "69") (name "unconnected-(LED3-DOUT-Pad1)") (class "Default")
      (node (ref "LED3") (pin "1") (pinfunction "DOUT_1") (pintype "passive"))
    )
    (net (code "70") (name "unconnected-(U2-NC-Pad5)") (class "Default")
      (node (ref "U2") (pin "5") (pinfunction "NC_5") (pintype "passive+no_connect"))
    )
    (net (code "71") (name "unconnected-(U4-PA4-Pad14)") (class "Default")
      (node (ref "U4") (pin "14") (pinfunction "PA4_14") (pintype "bidirectional"))
    )
    (net (code "72") (name "unconnected-(U4-PB2-Pad20)") (class "Default")
      (node (ref "U4") (pin "20") (pinfunction "PB2_20") (pintype "bidirectional+no_connect"))
    )
    (net (code "73") (name "unconnected-(U4-PC13-Pad2)") (class "Default")
      (node (ref "U4") (pin "2") (pinfunction "PC13_2") (pintype "bidirectional+no_connect"))
    )
    (net (code "74") (name "unconnected-(U4-PC14-OSC32_IN-Pad3)") (class "Default")
      (node (ref "U4") (pin "3") (pinfunction "PC14-OSC32_IN_3") (pintype "bidirectional+no_connect"))
    )
    (net (code "75") (name "unconnected-(U4-PC15-OSC32_OUT-Pad4)") (class "Default")
      (node (ref "U4") (pin "4") (pinfunction "PC15-OSC32_OUT_4") (pintype "bidirectional+no_connect"))
    )
  )
)
